# imu-extend.net
KiCad netlist of a schematic drawn in Altium Designer
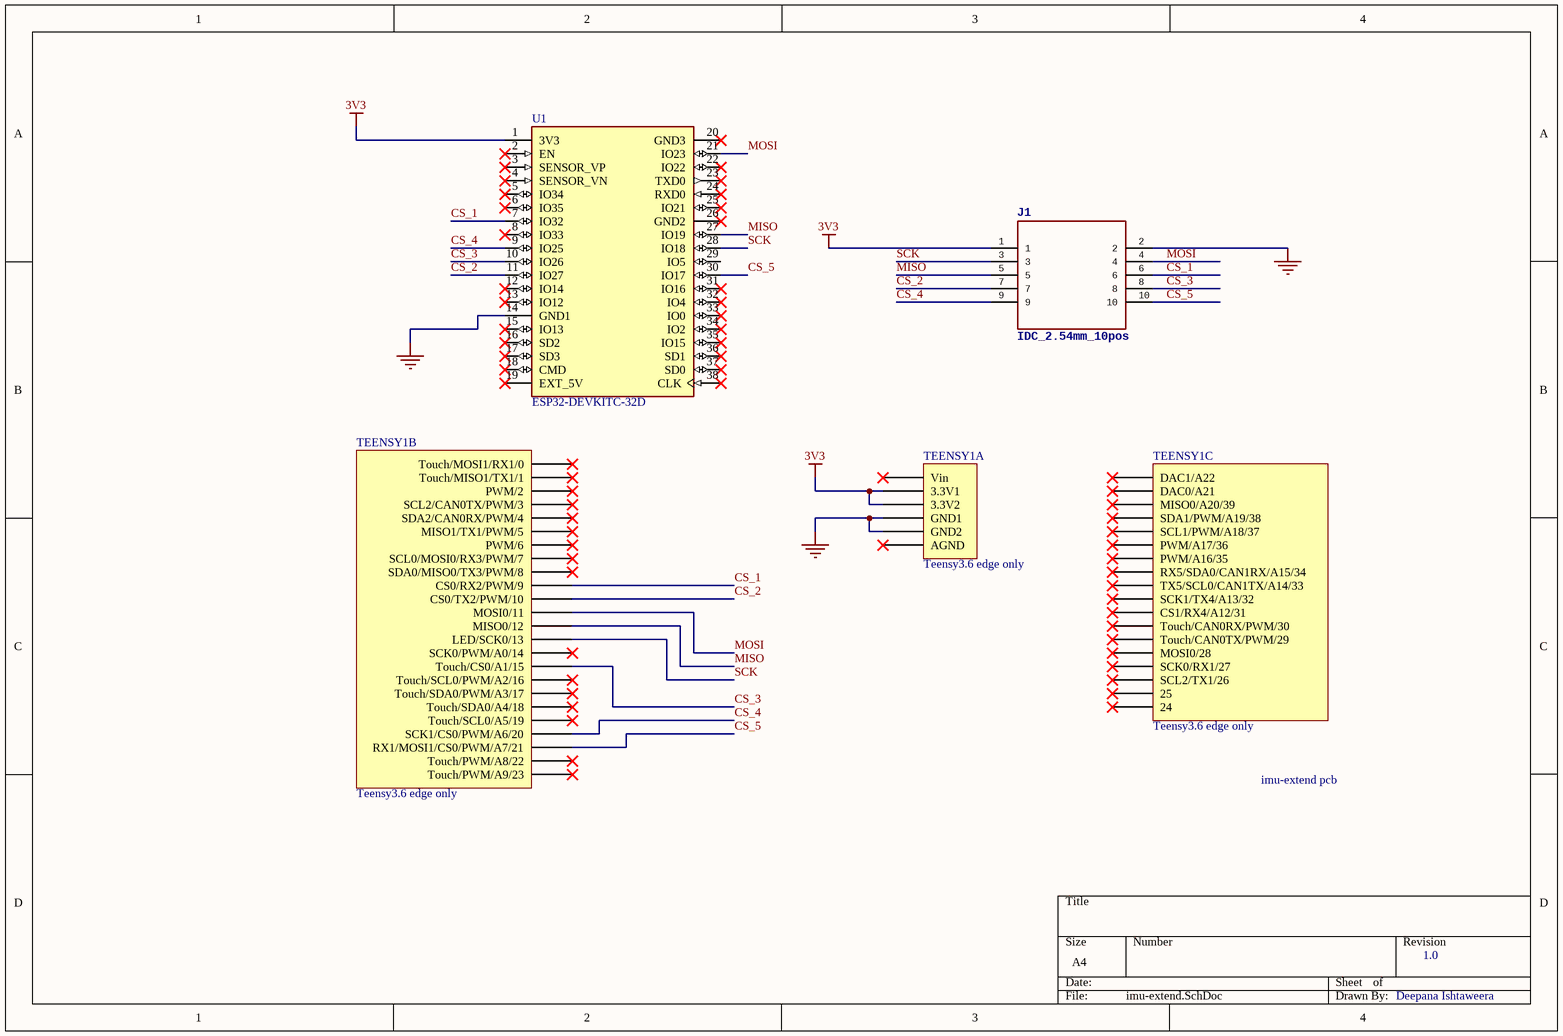
[diagram p0: imu-extend.SchDoc]

(export (version "E")
  (design (tool "Eeschema 10.0.6"))
  (components
    (comp (ref "J1")
      (value "IDC_2.54mm_10pos")
      (footprint "IDC_2.54_10")
      (description "5x2 male connector (2.54mm)")
      (libsource (lib "imu-pcb-lib") (part "IDC_2.54mm_10pos"))
    )
    (comp (ref "TEENSY1")
      (value "Teensy3.6 edge only")
      (footprint "Teensy3.6-edgeonly")
      (libsource (lib "teensy3.6") (part "Teensy3.6 edge only"))
    )
    (comp (ref "U1")
      (value "ESP32-DEVKITC-32D")
      (footprint "MODULE_ESP32-DEVKITC-32D")
      (fields (field (name "MF") "Espressif Systems"))
      (libsource (lib "ESP32-DEVKITC-32D") (part "ESP32-DEVKITC-32D"))
    )
  )
  (nets
    (net (code "1") (name "/CS_1") (class "Default")
      (node (ref "J1") (pin "6") (pinfunction "6_6") (pintype "passive"))
      (node (ref "TEENSY1") (pin "9") (pinfunction "CS0/RX2/PWM/9_9") (pintype "passive"))
      (node (ref "U1") (pin "7") (pinfunction "IO32_7") (pintype "bidirectional"))
    )
    (net (code "2") (name "/CS_2") (class "Default")
      (node (ref "J1") (pin "7") (pinfunction "7_7") (pintype "passive"))
      (node (ref "TEENSY1") (pin "10") (pinfunction "CS0/TX2/PWM/10_10") (pintype "passive"))
      (node (ref "U1") (pin "11") (pinfunction "IO27_11") (pintype "bidirectional"))
    )
    (net (code "3") (name "/CS_3") (class "Default")
      (node (ref "J1") (pin "8") (pinfunction "8_8") (pintype "passive"))
      (node (ref "TEENSY1") (pin "15") (pinfunction "Touch/CS0/A1/15_15") (pintype "passive"))
      (node (ref "U1") (pin "10") (pinfunction "IO26_10") (pintype "bidirectional"))
    )
    (net (code "4") (name "/CS_4") (class "Default")
      (node (ref "J1") (pin "9") (pinfunction "9_9") (pintype "passive"))
      (node (ref "TEENSY1") (pin "20") (pinfunction "SCK1/CS0/PWM/A6/20_20") (pintype "passive"))
      (node (ref "U1") (pin "9") (pinfunction "IO25_9") (pintype "bidirectional"))
    )
    (net (code "5") (name "/CS_5") (class "Default")
      (node (ref "J1") (pin "10") (pinfunction "10_10") (pintype "passive"))
      (node (ref "TEENSY1") (pin "21") (pinfunction "RX1/MOSI1/CS0/PWM/A7/21_21") (pintype "passive"))
      (node (ref "U1") (pin "30") (pinfunction "IO17_30") (pintype "bidirectional"))
    )
    (net (code "6") (name "/MISO") (class "Default")
      (node (ref "J1") (pin "5") (pinfunction "5_5") (pintype "passive"))
      (node (ref "TEENSY1") (pin "12") (pinfunction "MISO0/12_12") (pintype "passive"))
      (node (ref "U1") (pin "27") (pinfunction "IO19_27") (pintype "bidirectional"))
    )
    (net (code "7") (name "/MOSI") (class "Default")
      (node (ref "J1") (pin "4") (pinfunction "4_4") (pintype "passive"))
      (node (ref "TEENSY1") (pin "11") (pinfunction "MOSI0/11_11") (pintype "passive"))
      (node (ref "U1") (pin "21") (pinfunction "IO23_21") (pintype "bidirectional"))
    )
    (net (code "8") (name "/SCK") (class "Default")
      (node (ref "J1") (pin "3") (pinfunction "3_3") (pintype "passive"))
      (node (ref "TEENSY1") (pin "13") (pinfunction "LED/SCK0/13_13") (pintype "passive"))
      (node (ref "U1") (pin "28") (pinfunction "IO18_28") (pintype "bidirectional"))
    )
    (net (code "9") (name "3V3") (class "Default")
      (node (ref "J1") (pin "1") (pinfunction "1_1") (pintype "passive"))
      (node (ref "TEENSY1") (pin "3.3V1") (pinfunction "3.3V1_3.3V1") (pintype "power_in"))
      (node (ref "TEENSY1") (pin "3.3V2") (pinfunction "3.3V2_3.3V2") (pintype "power_in"))
      (node (ref "U1") (pin "1") (pinfunction "3V3_1") (pintype "power_in"))
    )
    (net (code "10") (name "GND") (class "Default")
      (node (ref "J1") (pin "2") (pinfunction "2_2") (pintype "passive"))
      (node (ref "TEENSY1") (pin "GND1") (pinfunction "GND1_GND1") (pintype "power_in"))
      (node (ref "TEENSY1") (pin "GND2") (pinfunction "GND2_GND2") (pintype "power_in"))
      (node (ref "U1") (pin "14") (pinfunction "GND1_14") (pintype "power_in"))
    )
    (net (code "11") (name "unconnected-(TEENSY1-Pad24)") (class "Default")
      (node (ref "TEENSY1") (pin "24") (pinfunction "24_24") (pintype "passive+no_connect"))
    )
    (net (code "12") (name "unconnected-(TEENSY1-Pad25)") (class "Default")
      (node (ref "TEENSY1") (pin "25") (pinfunction "25_25") (pintype "passive+no_connect"))
    )
    (net (code "13") (name "unconnected-(TEENSY1-PadAGND)") (class "Default")
      (node (ref "TEENSY1") (pin "AGND") (pinfunction "AGND_AGND") (pintype "power_in+no_connect"))
    )
    (net (code "14") (name "unconnected-(TEENSY1A-Vin-PadVIN)") (class "Default")
      (node (ref "TEENSY1") (pin "VIN") (pinfunction "Vin_VIN") (pintype "power_in+no_connect"))
    )
    (net (code "15") (name "unconnected-(TEENSY1B-MISO1{slash}TX1{slash}PWM{slash}5-Pad5)") (class "Default")
      (node (ref "TEENSY1") (pin "5") (pinfunction "MISO1/TX1/PWM/5_5") (pintype "passive+no_connect"))
    )
    (net (code "16") (name "unconnected-(TEENSY1B-PWM{slash}2-Pad2)") (class "Default")
      (node (ref "TEENSY1") (pin "2") (pinfunction "PWM/2_2") (pintype "passive+no_connect"))
    )
    (net (code "17") (name "unconnected-(TEENSY1B-PWM{slash}6-Pad6)") (class "Default")
      (node (ref "TEENSY1") (pin "6") (pinfunction "PWM/6_6") (pintype "passive+no_connect"))
    )
    (net (code "18") (name "unconnected-(TEENSY1B-SCK0{slash}PWM{slash}A0{slash}14-Pad14)") (class "Default")
      (node (ref "TEENSY1") (pin "14") (pinfunction "SCK0/PWM/A0/14_14") (pintype "passive+no_connect"))
    )
    (net (code "19") (name "unconnected-(TEENSY1B-SCL0{slash}MOSI0{slash}RX3{slash}PWM{slash}7-Pad7)") (class "Default")
      (node (ref "TEENSY1") (pin "7") (pinfunction "SCL0/MOSI0/RX3/PWM/7_7") (pintype "passive+no_connect"))
    )
    (net (code "20") (name "unconnected-(TEENSY1B-SCL2{slash}CAN0TX{slash}PWM{slash}3-Pad3)") (class "Default")
      (node (ref "TEENSY1") (pin "3") (pinfunction "SCL2/CAN0TX/PWM/3_3") (pintype "passive+no_connect"))
    )
    (net (code "21") (name "unconnected-(TEENSY1B-SDA0{slash}MISO0{slash}TX3{slash}PWM{slash}8-Pad8)") (class "Default")
      (node (ref "TEENSY1") (pin "8") (pinfunction "SDA0/MISO0/TX3/PWM/8_8") (pintype "passive+no_connect"))
    )
    (net (code "22") (name "unconnected-(TEENSY1B-SDA2{slash}CAN0RX{slash}PWM{slash}4-Pad4)") (class "Default")
      (node (ref "TEENSY1") (pin "4") (pinfunction "SDA2/CAN0RX/PWM/4_4") (pintype "passive+no_connect"))
    )
    (net (code "23") (name "unconnected-(TEENSY1B-Touch{slash}MISO1{slash}TX1{slash}1-Pad1)") (class "Default")
      (node (ref "TEENSY1") (pin "1") (pinfunction "Touch/MISO1/TX1/1_1") (pintype "passive+no_connect"))
    )
    (net (code "24") (name "unconnected-(TEENSY1B-Touch{slash}MOSI1{slash}RX1{slash}0-Pad0)") (class "Default")
      (node (ref "TEENSY1") (pin "0") (pinfunction "Touch/MOSI1/RX1/0_0") (pintype "passive+no_connect"))
    )
    (net (code "25") (name "unconnected-(TEENSY1B-Touch{slash}PWM{slash}A8{slash}22-Pad22)") (class "Default")
      (node (ref "TEENSY1") (pin "22") (pinfunction "Touch/PWM/A8/22_22") (pintype "passive+no_connect"))
    )
    (net (code "26") (name "unconnected-(TEENSY1B-Touch{slash}PWM{slash}A9{slash}23-Pad23)") (class "Default")
      (node (ref "TEENSY1") (pin "23") (pinfunction "Touch/PWM/A9/23_23") (pintype "passive+no_connect"))
    )
    (net (code "27") (name "unconnected-(TEENSY1B-Touch{slash}SCL0{slash}A5{slash}19-Pad19)") (class "Default")
      (node (ref "TEENSY1") (pin "19") (pinfunction "Touch/SCL0/A5/19_19") (pintype "passive+no_connect"))
    )
    (net (code "28") (name "unconnected-(TEENSY1B-Touch{slash}SCL0{slash}PWM{slash}A2{slash}16-Pad16)") (class "Default")
      (node (ref "TEENSY1") (pin "16") (pinfunction "Touch/SCL0/PWM/A2/16_16") (pintype "passive+no_connect"))
    )
    (net (code "29") (name "unconnected-(TEENSY1B-Touch{slash}SDA0{slash}A4{slash}18-Pad18)") (class "Default")
      (node (ref "TEENSY1") (pin "18") (pinfunction "Touch/SDA0/A4/18_18") (pintype "passive+no_connect"))
    )
    (net (code "30") (name "unconnected-(TEENSY1B-Touch{slash}SDA0{slash}PWM{slash}A3{slash}17-Pad17)") (class "Default")
      (node (ref "TEENSY1") (pin "17") (pinfunction "Touch/SDA0/PWM/A3/17_17") (pintype "passive+no_connect"))
    )
    (net (code "31") (name "unconnected-(TEENSY1C-CS1{slash}RX4{slash}A12{slash}31-Pad31)") (class "Default")
      (node (ref "TEENSY1") (pin "31") (pinfunction "CS1/RX4/A12/31_31") (pintype "passive+no_connect"))
    )
    (net (code "32") (name "unconnected-(TEENSY1C-DAC0{slash}A21-PadA21)") (class "Default")
      (node (ref "TEENSY1") (pin "A21") (pinfunction "DAC0/A21_A21") (pintype "passive+no_connect"))
    )
    (net (code "33") (name "unconnected-(TEENSY1C-DAC1{slash}A22-PadA22)") (class "Default")
      (node (ref "TEENSY1") (pin "A22") (pinfunction "DAC1/A22_A22") (pintype "passive+no_connect"))
    )
    (net (code "34") (name "unconnected-(TEENSY1C-MISO0{slash}A20{slash}39-Pad39)") (class "Default")
      (node (ref "TEENSY1") (pin "39") (pinfunction "MISO0/A20/39_39") (pintype "passive+no_connect"))
    )
    (net (code "35") (name "unconnected-(TEENSY1C-MOSI0{slash}28-Pad28)") (class "Default")
      (node (ref "TEENSY1") (pin "28") (pinfunction "MOSI0/28_28") (pintype "passive+no_connect"))
    )
    (net (code "36") (name "unconnected-(TEENSY1C-PWM{slash}A16{slash}35-Pad35)") (class "Default")
      (node (ref "TEENSY1") (pin "35") (pinfunction "PWM/A16/35_35") (pintype "passive+no_connect"))
    )
    (net (code "37") (name "unconnected-(TEENSY1C-PWM{slash}A17{slash}36-Pad36)") (class "Default")
      (node (ref "TEENSY1") (pin "36") (pinfunction "PWM/A17/36_36") (pintype "passive+no_connect"))
    )
    (net (code "38") (name "unconnected-(TEENSY1C-RX5{slash}SDA0{slash}CAN1RX{slash}A15{slash}34-Pad34)") (class "Default")
      (node (ref "TEENSY1") (pin "34") (pinfunction "RX5/SDA0/CAN1RX/A15/34_34") (pintype "passive+no_connect"))
    )
    (net (code "39") (name "unconnected-(TEENSY1C-SCK0{slash}RX1{slash}27-Pad27)") (class "Default")
      (node (ref "TEENSY1") (pin "27") (pinfunction "SCK0/RX1/27_27") (pintype "passive+no_connect"))
    )
    (net (code "40") (name "unconnected-(TEENSY1C-SCK1{slash}TX4{slash}A13{slash}32-Pad32)") (class "Default")
      (node (ref "TEENSY1") (pin "32") (pinfunction "SCK1/TX4/A13/32_32") (pintype "passive+no_connect"))
    )
    (net (code "41") (name "unconnected-(TEENSY1C-SCL1{slash}PWM{slash}A18{slash}37-Pad37)") (class "Default")
      (node (ref "TEENSY1") (pin "37") (pinfunction "SCL1/PWM/A18/37_37") (pintype "passive+no_connect"))
    )
    (net (code "42") (name "unconnected-(TEENSY1C-SCL2{slash}TX1{slash}26-Pad26)") (class "Default")
      (node (ref "TEENSY1") (pin "26") (pinfunction "SCL2/TX1/26_26") (pintype "passive+no_connect"))
    )
    (net (code "43") (name "unconnected-(TEENSY1C-SDA1{slash}PWM{slash}A19{slash}38-Pad38)") (class "Default")
      (node (ref "TEENSY1") (pin "38") (pinfunction "SDA1/PWM/A19/38_38") (pintype "passive+no_connect"))
    )
    (net (code "44") (name "unconnected-(TEENSY1C-TX5{slash}SCL0{slash}CAN1TX{slash}A14{slash}33-Pad33)") (class "Default")
      (node (ref "TEENSY1") (pin "33") (pinfunction "TX5/SCL0/CAN1TX/A14/33_33") (pintype "passive+no_connect"))
    )
    (net (code "45") (name "unconnected-(TEENSY1C-Touch{slash}CAN0RX{slash}PWM{slash}30-Pad30)") (class "Default")
      (node (ref "TEENSY1") (pin "30") (pinfunction "Touch/CAN0RX/PWM/30_30") (pintype "passive+no_connect"))
    )
    (net (code "46") (name "unconnected-(TEENSY1C-Touch{slash}CAN0TX{slash}PWM{slash}29-Pad29)") (class "Default")
      (node (ref "TEENSY1") (pin "29") (pinfunction "Touch/CAN0TX/PWM/29_29") (pintype "passive+no_connect"))
    )
    (net (code "47") (name "unconnected-(U1-CLK-Pad38)") (class "Default")
      (node (ref "U1") (pin "38") (pinfunction "CLK_38") (pintype "input+no_connect"))
    )
    (net (code "48") (name "unconnected-(U1-CMD-Pad18)") (class "Default")
      (node (ref "U1") (pin "18") (pinfunction "CMD_18") (pintype "bidirectional+no_connect"))
    )
    (net (code "49") (name "unconnected-(U1-EN-Pad2)") (class "Default")
      (node (ref "U1") (pin "2") (pinfunction "EN_2") (pintype "input+no_connect"))
    )
    (net (code "50") (name "unconnected-(U1-EXT_5V-Pad19)") (class "Default")
      (node (ref "U1") (pin "19") (pinfunction "EXT_5V_19") (pintype "power_in+no_connect"))
    )
    (net (code "51") (name "unconnected-(U1-GND2-Pad26)") (class "Default")
      (node (ref "U1") (pin "26") (pinfunction "GND2_26") (pintype "power_in+no_connect"))
    )
    (net (code "52") (name "unconnected-(U1-GND3-Pad20)") (class "Default")
      (node (ref "U1") (pin "20") (pinfunction "GND3_20") (pintype "power_in+no_connect"))
    )
    (net (code "53") (name "unconnected-(U1-IO0-Pad33)") (class "Default")
      (node (ref "U1") (pin "33") (pinfunction "IO0_33") (pintype "bidirectional+no_connect"))
    )
    (net (code "54") (name "unconnected-(U1-IO2-Pad34)") (class "Default")
      (node (ref "U1") (pin "34") (pinfunction "IO2_34") (pintype "bidirectional+no_connect"))
    )
    (net (code "55") (name "unconnected-(U1-IO4-Pad32)") (class "Default")
      (node (ref "U1") (pin "32") (pinfunction "IO4_32") (pintype "bidirectional+no_connect"))
    )
    (net (code "56") (name "unconnected-(U1-IO5-Pad29)") (class "Default")
      (node (ref "U1") (pin "29") (pinfunction "IO5_29") (pintype "bidirectional"))
    )
    (net (code "57") (name "unconnected-(U1-IO12-Pad13)") (class "Default")
      (node (ref "U1") (pin "13") (pinfunction "IO12_13") (pintype "bidirectional+no_connect"))
    )
    (net (code "58") (name "unconnected-(U1-IO13-Pad15)") (class "Default")
      (node (ref "U1") (pin "15") (pinfunction "IO13_15") (pintype "bidirectional+no_connect"))
    )
    (net (code "59") (name "unconnected-(U1-IO14-Pad12)") (class "Default")
      (node (ref "U1") (pin "12") (pinfunction "IO14_12") (pintype "bidirectional+no_connect"))
    )
    (net (code "60") (name "unconnected-(U1-IO15-Pad35)") (class "Default")
      (node (ref "U1") (pin "35") (pinfunction "IO15_35") (pintype "bidirectional+no_connect"))
    )
    (net (code "61") (name "unconnected-(U1-IO16-Pad31)") (class "Default")
      (node (ref "U1") (pin "31") (pinfunction "IO16_31") (pintype "bidirectional+no_connect"))
    )
    (net (code "62") (name "unconnected-(U1-IO21-Pad25)") (class "Default")
      (node (ref "U1") (pin "25") (pinfunction "IO21_25") (pintype "bidirectional+no_connect"))
    )
    (net (code "63") (name "unconnected-(U1-IO22-Pad22)") (class "Default")
      (node (ref "U1") (pin "22") (pinfunction "IO22_22") (pintype "bidirectional+no_connect"))
    )
    (net (code "64") (name "unconnected-(U1-IO33-Pad8)") (class "Default")
      (node (ref "U1") (pin "8") (pinfunction "IO33_8") (pintype "bidirectional+no_connect"))
    )
    (net (code "65") (name "unconnected-(U1-IO34-Pad5)") (class "Default")
      (node (ref "U1") (pin "5") (pinfunction "IO34_5") (pintype "bidirectional+no_connect"))
    )
    (net (code "66") (name "unconnected-(U1-IO35-Pad6)") (class "Default")
      (node (ref "U1") (pin "6") (pinfunction "IO35_6") (pintype "bidirectional+no_connect"))
    )
    (net (code "67") (name "unconnected-(U1-RXD0-Pad24)") (class "Default")
      (node (ref "U1") (pin "24") (pinfunction "RXD0_24") (pintype "input+no_connect"))
    )
    (net (code "68") (name "unconnected-(U1-SD0-Pad37)") (class "Default")
      (node (ref "U1") (pin "37") (pinfunction "SD0_37") (pintype "bidirectional+no_connect"))
    )
    (net (code "69") (name "unconnected-(U1-SD1-Pad36)") (class "Default")
      (node (ref "U1") (pin "36") (pinfunction "SD1_36") (pintype "bidirectional+no_connect"))
    )
    (net (code "70") (name "unconnected-(U1-SD2-Pad16)") (class "Default")
      (node (ref "U1") (pin "16") (pinfunction "SD2_16") (pintype "bidirectional+no_connect"))
    )
    (net (code "71") (name "unconnected-(U1-SD3-Pad17)") (class "Default")
      (node (ref "U1") (pin "17") (pinfunction "SD3_17") (pintype "bidirectional+no_connect"))
    )
    (net (code "72") (name "unconnected-(U1-SENSOR_VN-Pad4)") (class "Default")
      (node (ref "U1") (pin "4") (pinfunction "SENSOR_VN_4") (pintype "input+no_connect"))
    )
    (net (code "73") (name "unconnected-(U1-SENSOR_VP-Pad3)") (class "Default")
      (node (ref "U1") (pin "3") (pinfunction "SENSOR_VP_3") (pintype "input+no_connect"))
    )
    (net (code "74") (name "unconnected-(U1-TXD0-Pad23)") (class "Default")
      (node (ref "U1") (pin "23") (pinfunction "TXD0_23") (pintype "output+no_connect"))
    )
  )
)
